# design.net
KiCad netlist of a schematic drawn in Altium Designer
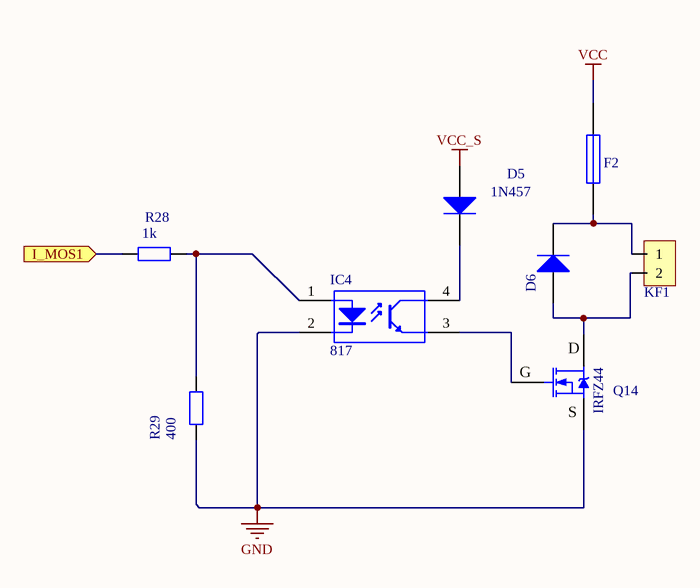
[diagram p0: 电机控制盒.SchDoc]

(export (version "E")
  (design (tool "Eeschema 10.0.6"))
  (components
    (comp (ref "D5")
      (value "1N457")
      (footprint "DO-35")
      (description "DIP,D0-35,额定电压70V,电流200mA")
      (fields
        (field (name "PART NUMBER") "102DG-00002AI.01")
        (field (name "ALLOW ALTENATIVE PART") "Y")
        (field (name "REMARK") "Verified by CRD（张宗良） check list V1.0")
        (field (name "MODIFY TIME") "2015年07月10号")
        (field (name "APPROVED") "YES")
      )
      (libsource (lib "IA-04") (part "Diode-CM-2-N2"))
    )
    (comp (ref "D6")
      (value "1N4007-E3/73")
      (footprint "DO-41")
      (description "DIP,DO-41,额定电压1000V,电流1A")
      (fields
        (field (name "PART NUMBER") "102DG-00002BS.01")
        (field (name "ALLOW ALTENATIVE PART") "Y")
        (field (name "REMARK") "Verified by CRD（张宗良） check list V1.0")
        (field (name "MODIFY TIME") "2016年08月22号")
        (field (name "APPROVED") "YES")
      )
      (libsource (lib "IA-04") (part "Diode-CM-2-N2"))
    )
    (comp (ref "F2")
      (value "R30-600")
      (footprint "FUSE-16R5X3RX24R9-TH")
      (description "DIP,16.5x24.9x3.0mm,额定电压30V,额定电流6A,触发电流12A,中速断")
      (fields
        (field (name "PART NUMBER") "102FP-00034BI.01")
        (field (name "ALLOW ALTENATIVE PART") "Y")
        (field (name "REMARK") "Verified by BU1（黄雄青） check list V1.0")
        (field (name "MODIFY TIME") "2015年07月10号")
        (field (name "APPROVED") "YES")
      )
      (libsource (lib "IA-04") (part "Fuse-2-NP"))
    )
    (comp (ref "IC4")
      (value "817")
      (footprint "DIP4-300")
      (description "线性光耦")
      (fields (field (name "版权归属") "源创客"))
      (libsource (lib "11.1 - 传感元件") (part "817"))
    )
    (comp (ref "KF1")
      (value "KF301-5.08-2p")
      (footprint "KF301-5.0-2P")
      (libsource (lib "KF接口") (part "KF301"))
    )
    (comp (ref "Q14")
      (value "IRFZ44")
      (footprint "TO220A")
      (description "N沟场效应管")
      (fields (field (name "版权归属") "源创客"))
      (libsource (lib "6.1   - 场效应管-可控硅") (part "IRF840"))
    )
    (comp (ref "R28")
      (value "1k")
      (footprint "RY0R25W")
      (description "DIP,阻值1M,精度±1%,AXIAL0.4,额定功率1/4W")
      (fields
        (field (name "PART NUMBER") "102RO-00018BW.01")
        (field (name "ALLOW ALTENATIVE PART") "Y")
        (field (name "REMARK") "Verified by BU3（吴明徽）check list V1.0")
        (field (name "MODIFY TIME") "2015年11月30号")
        (field (name "APPROVED") "YES")
      )
      (libsource (lib "") (part "RES-2-NP_1"))
    )
    (comp (ref "R29")
      (value "400")
      (footprint "RY0R25W")
      (description "DIP,阻值1M,精度±1%,AXIAL0.4,额定功率1/4W")
      (fields
        (field (name "PART NUMBER") "102RO-00018BW.01")
        (field (name "ALLOW ALTENATIVE PART") "Y")
        (field (name "REMARK") "Verified by BU3（吴明徽）check list V1.0")
        (field (name "MODIFY TIME") "2015年11月30号")
        (field (name "APPROVED") "YES")
      )
      (libsource (lib "IA-04") (part "RES-2-NP"))
    )
  )
  (nets
    (net (code "1") (name "/I_MOS1") (class "Default")
      (node (ref "R28") (pin "1") (pinfunction "1_1") (pintype "passive"))
    )
    (net (code "2") (name "GND") (class "Default")
      (node (ref "IC4") (pin "2") (pinfunction "K_2") (pintype "passive"))
      (node (ref "Q14") (pin "3") (pinfunction "S_3") (pintype "passive"))
      (node (ref "R29") (pin "1") (pinfunction "1_1") (pintype "passive"))
    )
    (net (code "3") (name "Net-(D6-Pad2)") (class "Default")
      (node (ref "D6") (pin "2") (pinfunction "2_2") (pintype "passive"))
      (node (ref "F2") (pin "1") (pinfunction "1_1") (pintype "passive"))
      (node (ref "KF1") (pin "1") (pinfunction "1_1") (pintype "passive"))
    )
    (net (code "4") (name "Net-(IC4-A)") (class "Default")
      (node (ref "IC4") (pin "1") (pinfunction "A_1") (pintype "passive"))
      (node (ref "R28") (pin "2") (pinfunction "2_2") (pintype "passive"))
      (node (ref "R29") (pin "2") (pinfunction "2_2") (pintype "passive"))
    )
    (net (code "5") (name "Net-(IC4-C)") (class "Default")
      (node (ref "D5") (pin "2") (pinfunction "2_2") (pintype "passive"))
      (node (ref "IC4") (pin "4") (pinfunction "C_4") (pintype "passive"))
    )
    (net (code "6") (name "Net-(IC4-E)") (class "Default")
      (node (ref "IC4") (pin "3") (pinfunction "E_3") (pintype "passive"))
      (node (ref "Q14") (pin "1") (pinfunction "G_1") (pintype "passive"))
    )
    (net (code "7") (name "Net-(Q14-D)") (class "Default")
      (node (ref "D6") (pin "1") (pinfunction "1_1") (pintype "passive"))
      (node (ref "KF1") (pin "2") (pinfunction "2_2") (pintype "passive"))
      (node (ref "Q14") (pin "2") (pinfunction "D_2") (pintype "passive"))
    )
    (net (code "8") (name "VCC") (class "Default")
      (node (ref "F2") (pin "2") (pinfunction "2_2") (pintype "passive"))
    )
    (net (code "9") (name "VCC_S") (class "Default")
      (node (ref "D5") (pin "1") (pinfunction "1_1") (pintype "passive"))
    )
  )
)
